# power.net
KiCad netlist of a schematic drawn in Altium Designer
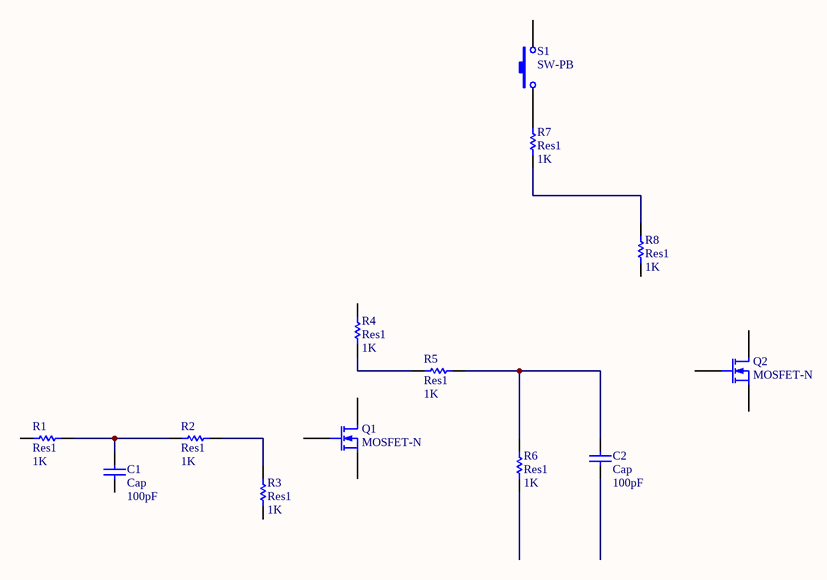
[diagram p0: power.SchDoc]

(export (version "E")
  (design (tool "Eeschema 10.0.6"))
  (components
    (comp (ref "C1")
      (value "Cap")
      (footprint "RAD-0.3")
      (description "Capacitor")
      (fields (field (name "ALTIUM_VALUE") "100pF") (field (name "PUBLISHER") "Altium Limited"))
      (libsource (lib "Miscellaneous Devices") (part "Cap"))
    )
    (comp (ref "C2")
      (value "Cap")
      (footprint "RAD-0.3")
      (description "Capacitor")
      (fields (field (name "ALTIUM_VALUE") "100pF") (field (name "PUBLISHER") "Altium Limited"))
      (libsource (lib "Miscellaneous Devices") (part "Cap"))
    )
    (comp (ref "Q1")
      (value "MOSFET-N")
      (footprint "E3")
      (description "N-Channel MOSFET")
      (fields (field (name "PUBLISHER") "Altium Limited"))
      (libsource (lib "Miscellaneous Devices") (part "MOSFET-N"))
    )
    (comp (ref "Q2")
      (value "MOSFET-N")
      (footprint "E3")
      (description "N-Channel MOSFET")
      (fields (field (name "PUBLISHER") "Altium Limited"))
      (libsource (lib "Miscellaneous Devices") (part "MOSFET-N"))
    )
    (comp (ref "R1")
      (value "Res1")
      (footprint "AXIAL-0.3")
      (description "Resistor")
      (fields (field (name "ALTIUM_VALUE") "1K") (field (name "PUBLISHER") "Altium Limited"))
      (libsource (lib "Miscellaneous Devices") (part "Res1"))
    )
    (comp (ref "R2")
      (value "Res1")
      (footprint "AXIAL-0.3")
      (description "Resistor")
      (fields (field (name "ALTIUM_VALUE") "1K") (field (name "PUBLISHER") "Altium Limited"))
      (libsource (lib "Miscellaneous Devices") (part "Res1"))
    )
    (comp (ref "R3")
      (value "Res1")
      (footprint "AXIAL-0.3")
      (description "Resistor")
      (fields (field (name "ALTIUM_VALUE") "1K") (field (name "PUBLISHER") "Altium Limited"))
      (libsource (lib "Miscellaneous Devices") (part "Res1"))
    )
    (comp (ref "R4")
      (value "Res1")
      (footprint "AXIAL-0.3")
      (description "Resistor")
      (fields (field (name "ALTIUM_VALUE") "1K") (field (name "PUBLISHER") "Altium Limited"))
      (libsource (lib "Miscellaneous Devices") (part "Res1"))
    )
    (comp (ref "R5")
      (value "Res1")
      (footprint "AXIAL-0.3")
      (description "Resistor")
      (fields (field (name "ALTIUM_VALUE") "1K") (field (name "PUBLISHER") "Altium Limited"))
      (libsource (lib "Miscellaneous Devices") (part "Res1"))
    )
    (comp (ref "R6")
      (value "Res1")
      (footprint "AXIAL-0.3")
      (description "Resistor")
      (fields (field (name "ALTIUM_VALUE") "1K") (field (name "PUBLISHER") "Altium Limited"))
      (libsource (lib "Miscellaneous Devices") (part "Res1"))
    )
    (comp (ref "R7")
      (value "Res1")
      (footprint "AXIAL-0.3")
      (description "Resistor")
      (fields (field (name "ALTIUM_VALUE") "1K") (field (name "PUBLISHER") "Altium Limited"))
      (libsource (lib "Miscellaneous Devices") (part "Res1"))
    )
    (comp (ref "R8")
      (value "Res1")
      (footprint "AXIAL-0.3")
      (description "Resistor")
      (fields (field (name "ALTIUM_VALUE") "1K") (field (name "PUBLISHER") "Altium Limited"))
      (libsource (lib "Miscellaneous Devices") (part "Res1"))
    )
    (comp (ref "S1")
      (value "SW-PB")
      (footprint "SPST-2")
      (description "Switch")
      (fields (field (name "PUBLISHER") "Altium Limited"))
      (libsource (lib "Miscellaneous Devices") (part "SW-PB"))
    )
  )
  (nets
    (net (code "1") (name "Net-(C1-Pad2)") (class "Default")
      (node (ref "C1") (pin "2") (pinfunction "2_2") (pintype "passive"))
      (node (ref "R1") (pin "2") (pinfunction "2_2") (pintype "passive"))
      (node (ref "R2") (pin "1") (pinfunction "1_1") (pintype "passive"))
    )
    (net (code "2") (name "Net-(C2-Pad2)") (class "Default")
      (node (ref "C2") (pin "2") (pinfunction "2_2") (pintype "passive"))
      (node (ref "R5") (pin "1") (pinfunction "1_1") (pintype "passive"))
      (node (ref "R6") (pin "1") (pinfunction "1_1") (pintype "passive"))
    )
    (net (code "3") (name "Net-(R2-Pad2)") (class "Default")
      (node (ref "R2") (pin "2") (pinfunction "2_2") (pintype "passive"))
      (node (ref "R3") (pin "2") (pinfunction "2_2") (pintype "passive"))
    )
    (net (code "4") (name "Net-(R4-Pad1)") (class "Default")
      (node (ref "R4") (pin "1") (pinfunction "1_1") (pintype "passive"))
      (node (ref "R5") (pin "2") (pinfunction "2_2") (pintype "passive"))
    )
    (net (code "5") (name "Net-(R7-Pad1)") (class "Default")
      (node (ref "R7") (pin "1") (pinfunction "1_1") (pintype "passive"))
      (node (ref "S1") (pin "1") (pinfunction "1_1") (pintype "passive"))
    )
    (net (code "6") (name "Net-(R7-Pad2)") (class "Default")
      (node (ref "R7") (pin "2") (pinfunction "2_2") (pintype "passive"))
      (node (ref "R8") (pin "1") (pinfunction "1_1") (pintype "passive"))
    )
    (net (code "7") (name "unconnected-(C1-Pad1)") (class "Default")
      (node (ref "C1") (pin "1") (pinfunction "1_1") (pintype "passive"))
    )
    (net (code "8") (name "unconnected-(C2-Pad1)") (class "Default")
      (node (ref "C2") (pin "1") (pinfunction "1_1") (pintype "passive"))
    )
    (net (code "9") (name "unconnected-(Q1-D-Pad1)") (class "Default")
      (node (ref "Q1") (pin "1") (pinfunction "D_1") (pintype "passive"))
    )
    (net (code "10") (name "unconnected-(Q1-G-Pad2)") (class "Default")
      (node (ref "Q1") (pin "2") (pinfunction "G_2") (pintype "passive"))
    )
    (net (code "11") (name "unconnected-(Q1-S-Pad3)") (class "Default")
      (node (ref "Q1") (pin "3") (pinfunction "S_3") (pintype "passive"))
    )
    (net (code "12") (name "unconnected-(Q2-D-Pad1)") (class "Default")
      (node (ref "Q2") (pin "1") (pinfunction "D_1") (pintype "passive"))
    )
    (net (code "13") (name "unconnected-(Q2-G-Pad2)") (class "Default")
      (node (ref "Q2") (pin "2") (pinfunction "G_2") (pintype "passive"))
    )
    (net (code "14") (name "unconnected-(Q2-S-Pad3)") (class "Default")
      (node (ref "Q2") (pin "3") (pinfunction "S_3") (pintype "passive"))
    )
    (net (code "15") (name "unconnected-(R1-Pad1)") (class "Default")
      (node (ref "R1") (pin "1") (pinfunction "1_1") (pintype "passive"))
    )
    (net (code "16") (name "unconnected-(R3-Pad1)") (class "Default")
      (node (ref "R3") (pin "1") (pinfunction "1_1") (pintype "passive"))
    )
    (net (code "17") (name "unconnected-(R4-Pad2)") (class "Default")
      (node (ref "R4") (pin "2") (pinfunction "2_2") (pintype "passive"))
    )
    (net (code "18") (name "unconnected-(R6-Pad2)") (class "Default")
      (node (ref "R6") (pin "2") (pinfunction "2_2") (pintype "passive"))
    )
    (net (code "19") (name "unconnected-(R8-Pad2)") (class "Default")
      (node (ref "R8") (pin "2") (pinfunction "2_2") (pintype "passive"))
    )
    (net (code "20") (name "unconnected-(S1-Pad2)") (class "Default")
      (node (ref "S1") (pin "2") (pinfunction "2_2") (pintype "passive"))
    )
  )
)
